# midi_switcher_trs.net
KiCad netlist of a schematic drawn in EAGLE
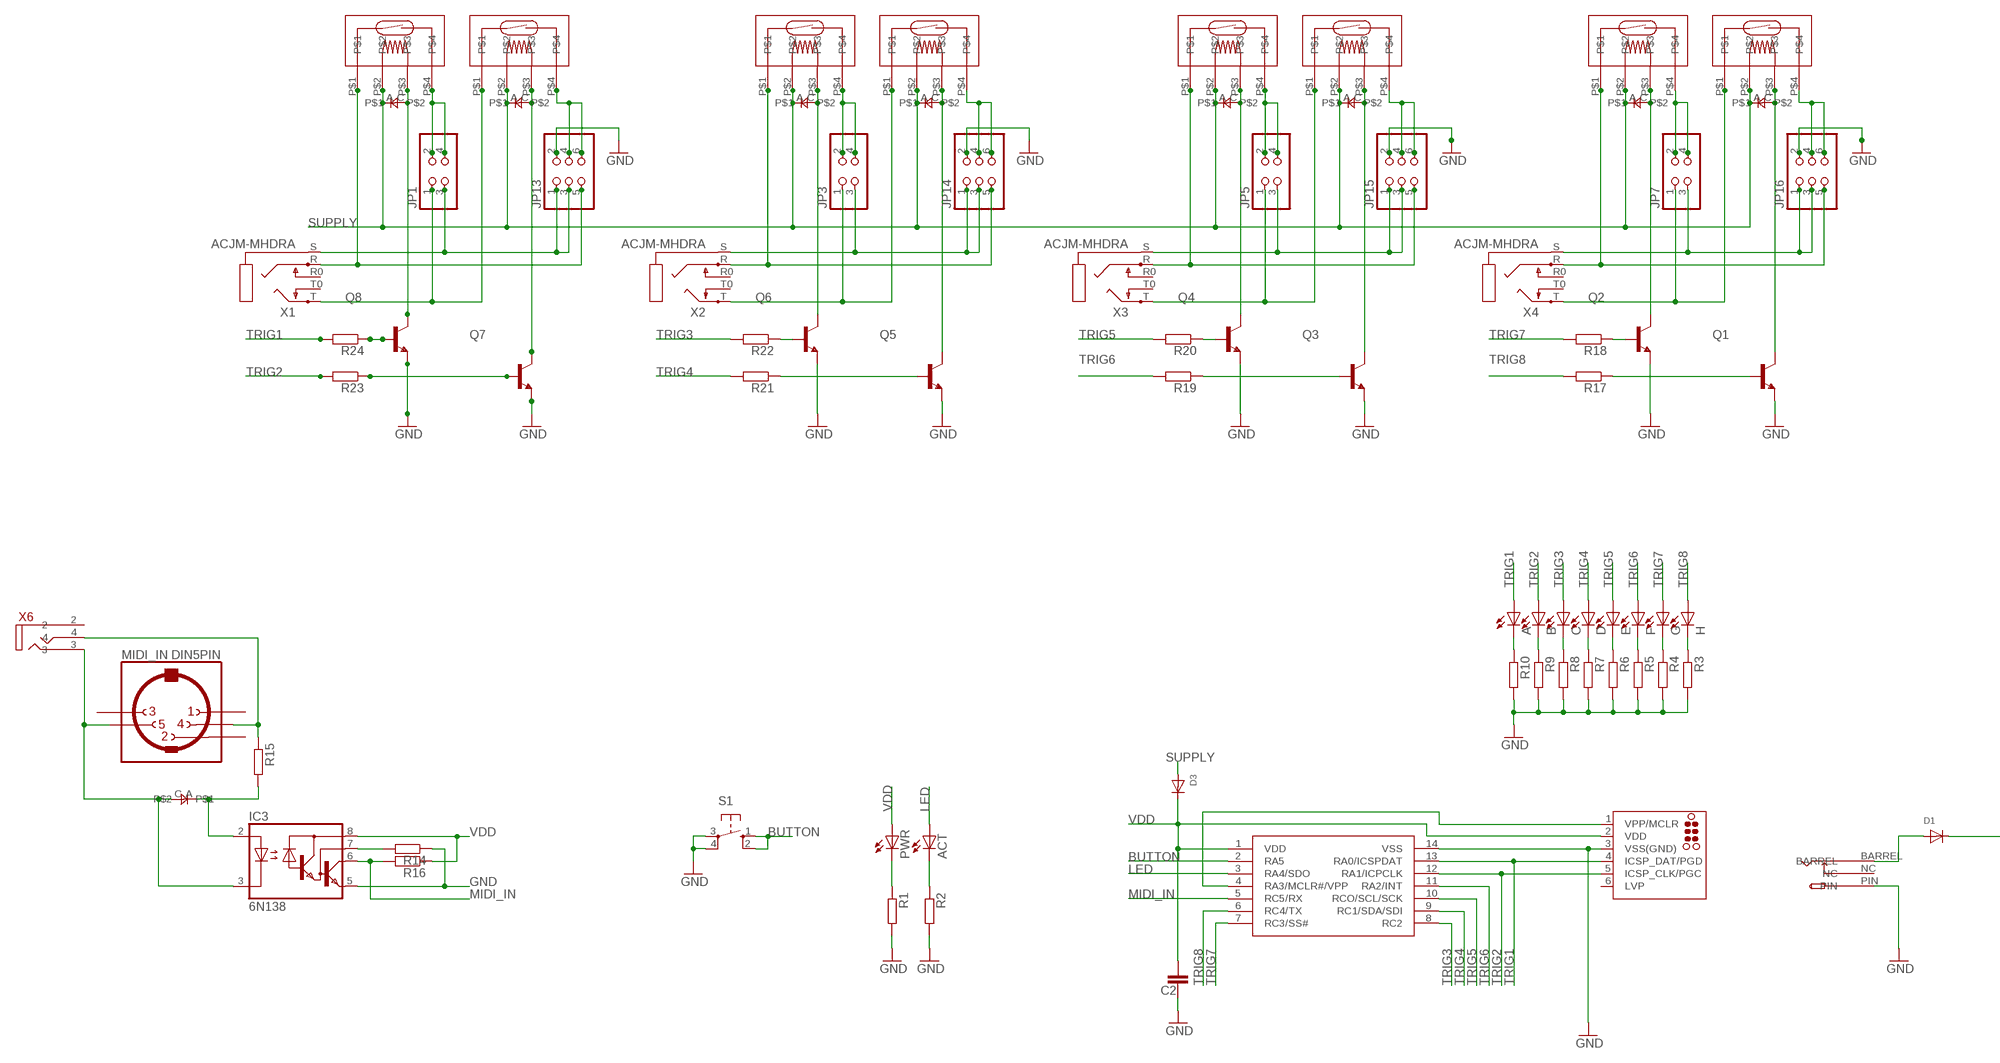
[diagram p0: schematic, sheet 1, part 1 of 2]
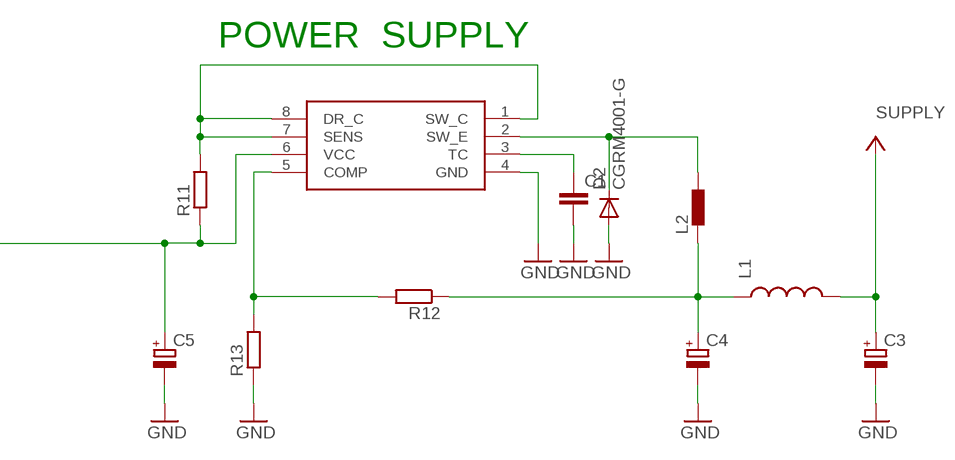
[diagram p1: schematic, sheet 1, part 2 of 2]

(export (version "E")
  (design (tool "Eeschema 10.0.6"))
  (components
    (comp (ref "A")
      (value "LED3MM")
      (footprint "eagle-import:LED3MM")
      (libsource (lib "eagle-import") (part "LED3MM"))
    )
    (comp (ref "ACT")
      (value "LED3MM")
      (footprint "eagle-import:LED3MM")
      (libsource (lib "eagle-import") (part "LED3MM"))
    )
    (comp (ref "B")
      (value "LED3MM")
      (footprint "eagle-import:LED3MM")
      (libsource (lib "eagle-import") (part "LED3MM"))
    )
    (comp (ref "C")
      (value "LED3MM")
      (footprint "eagle-import:LED3MM")
      (libsource (lib "eagle-import") (part "LED3MM"))
    )
    (comp (ref "C1")
      (value "C-EUC0805")
      (footprint "eagle-import:C0805")
      (libsource (lib "eagle-import") (part "C-EUC0805"))
    )
    (comp (ref "C2")
      (value "C-EUC0805")
      (footprint "eagle-import:C0805")
      (libsource (lib "eagle-import") (part "C-EUC0805"))
    )
    (comp (ref "C3")
      (value "CPOL-EUE2.5-7")
      (footprint "eagle-import:E2,5-7")
      (libsource (lib "eagle-import") (part "CPOL-EUE2.5-7"))
    )
    (comp (ref "C4")
      (value "CPOL-EUE2.5-7")
      (footprint "eagle-import:E2,5-7")
      (libsource (lib "eagle-import") (part "CPOL-EUE2.5-7"))
    )
    (comp (ref "C5")
      (value "CPOL-EUE2.5-7")
      (footprint "eagle-import:E2,5-7")
      (libsource (lib "eagle-import") (part "CPOL-EUE2.5-7"))
    )
    (comp (ref "D")
      (value "LED3MM")
      (footprint "eagle-import:LED3MM")
      (libsource (lib "eagle-import") (part "LED3MM"))
    )
    (comp (ref "D1")
      (value "DIODESOD-123")
      (footprint "eagle-import:SOD-123")
      (libsource (lib "eagle-import") (part "DIODESOD-123"))
    )
    (comp (ref "D2")
      (value "CGRM4001-G")
      (footprint "eagle-import:SOD-123_MINI-SMA")
      (libsource (lib "eagle-import") (part "CGRM400-G1"))
    )
    (comp (ref "D3")
      (value "DIODESOD-123")
      (footprint "eagle-import:SOD-123")
      (libsource (lib "eagle-import") (part "DIODESOD-123"))
    )
    (comp (ref "D4")
      (value "0805DIODE")
      (footprint "eagle-import:0805DIODE")
      (libsource (lib "eagle-import") (part "0805DIODE"))
    )
    (comp (ref "D5")
      (value "0805DIODE")
      (footprint "eagle-import:0805DIODE")
      (libsource (lib "eagle-import") (part "0805DIODE"))
    )
    (comp (ref "D6")
      (value "0805DIODE")
      (footprint "eagle-import:0805DIODE")
      (libsource (lib "eagle-import") (part "0805DIODE"))
    )
    (comp (ref "D7")
      (value "0805DIODE")
      (footprint "eagle-import:0805DIODE")
      (libsource (lib "eagle-import") (part "0805DIODE"))
    )
    (comp (ref "D8")
      (value "0805DIODE")
      (footprint "eagle-import:0805DIODE")
      (libsource (lib "eagle-import") (part "0805DIODE"))
    )
    (comp (ref "D9")
      (value "0805DIODE")
      (footprint "eagle-import:0805DIODE")
      (libsource (lib "eagle-import") (part "0805DIODE"))
    )
    (comp (ref "D10")
      (value "0805DIODE")
      (footprint "eagle-import:0805DIODE")
      (libsource (lib "eagle-import") (part "0805DIODE"))
    )
    (comp (ref "D11")
      (value "0805DIODE")
      (footprint "eagle-import:0805DIODE")
      (libsource (lib "eagle-import") (part "0805DIODE"))
    )
    (comp (ref "D12")
      (value "0805DIODE")
      (footprint "eagle-import:0805DIODE")
      (libsource (lib "eagle-import") (part "0805DIODE"))
    )
    (comp (ref "E")
      (value "LED3MM")
      (footprint "eagle-import:LED3MM")
      (libsource (lib "eagle-import") (part "LED3MM"))
    )
    (comp (ref "F")
      (value "LED3MM")
      (footprint "eagle-import:LED3MM")
      (libsource (lib "eagle-import") (part "LED3MM"))
    )
    (comp (ref "G")
      (value "LED3MM")
      (footprint "eagle-import:LED3MM")
      (libsource (lib "eagle-import") (part "LED3MM"))
    )
    (comp (ref "H")
      (value "LED3MM")
      (footprint "eagle-import:LED3MM")
      (libsource (lib "eagle-import") (part "LED3MM"))
    )
    (comp (ref "IC1")
      (value "SP34063A_BOOST_REG")
      (footprint "eagle-import:SOIC8")
      (libsource (lib "eagle-import") (part "SP34063A_BOOST_REG"))
    )
    (comp (ref "IC2")
      (value "PIC16F1825SO14")
      (footprint "eagle-import:SO14")
      (libsource (lib "eagle-import") (part "PIC16F1825SO14"))
    )
    (comp (ref "IC3")
      (value "6N138")
      (footprint "eagle-import:DIL08")
      (fields (field (name "MF") "VISHAY/TELEFUNKEN"))
      (libsource (lib "eagle-import") (part "6N138"))
    )
    (comp (ref "ICSP")
      (value "TC2030-MCP-NL")
      (footprint "eagle-import:TC2030-MCP-NL")
      (libsource (lib "eagle-import") (part "TC2030-MCP-NL"))
    )
    (comp (ref "JP1")
      (value "PINHD-2X2")
      (footprint "eagle-import:2X02")
      (libsource (lib "eagle-import") (part "PINHD-2X2"))
    )
    (comp (ref "JP3")
      (value "PINHD-2X2")
      (footprint "eagle-import:2X02")
      (libsource (lib "eagle-import") (part "PINHD-2X2"))
    )
    (comp (ref "JP5")
      (value "PINHD-2X2")
      (footprint "eagle-import:2X02")
      (libsource (lib "eagle-import") (part "PINHD-2X2"))
    )
    (comp (ref "JP7")
      (value "PINHD-2X2")
      (footprint "eagle-import:2X02")
      (libsource (lib "eagle-import") (part "PINHD-2X2"))
    )
    (comp (ref "JP13")
      (value "PINHD-2X3")
      (footprint "eagle-import:2X03")
      (libsource (lib "eagle-import") (part "PINHD-2X3"))
    )
    (comp (ref "JP14")
      (value "PINHD-2X3")
      (footprint "eagle-import:2X03")
      (libsource (lib "eagle-import") (part "PINHD-2X3"))
    )
    (comp (ref "JP15")
      (value "PINHD-2X3")
      (footprint "eagle-import:2X03")
      (libsource (lib "eagle-import") (part "PINHD-2X3"))
    )
    (comp (ref "JP16")
      (value "PINHD-2X3")
      (footprint "eagle-import:2X03")
      (libsource (lib "eagle-import") (part "PINHD-2X3"))
    )
    (comp (ref "L1")
      (value "INDUCTOR1210")
      (footprint "eagle-import:1210")
      (libsource (lib "eagle-import") (part "INDUCTOR1210"))
    )
    (comp (ref "L2")
      (value "DR1030")
      (footprint "eagle-import:DR1030")
      (libsource (lib "eagle-import") (part "DR1030"))
    )
    (comp (ref "MIDI_IN")
      (value "DIN5PIN")
      (footprint "eagle-import:EDGEDIN")
      (libsource (lib "eagle-import") (part "DIN5PIN"))
    )
    (comp (ref "PWR")
      (value "LED3MM")
      (footprint "eagle-import:LED3MM")
      (libsource (lib "eagle-import") (part "LED3MM"))
    )
    (comp (ref "Q1")
      (value "MMBT3904LT1-NPN-SOT23-BEC")
      (footprint "eagle-import:SOT23-BEC")
      (libsource (lib "eagle-import") (part "-NPN-SOT23-BECMMBT3904LT1"))
    )
    (comp (ref "Q2")
      (value "MMBT3904LT1-NPN-SOT23-BEC")
      (footprint "eagle-import:SOT23-BEC")
      (libsource (lib "eagle-import") (part "-NPN-SOT23-BECMMBT3904LT1"))
    )
    (comp (ref "Q3")
      (value "MMBT3904LT1-NPN-SOT23-BEC")
      (footprint "eagle-import:SOT23-BEC")
      (libsource (lib "eagle-import") (part "-NPN-SOT23-BECMMBT3904LT1"))
    )
    (comp (ref "Q4")
      (value "MMBT3904LT1-NPN-SOT23-BEC")
      (footprint "eagle-import:SOT23-BEC")
      (libsource (lib "eagle-import") (part "-NPN-SOT23-BECMMBT3904LT1"))
    )
    (comp (ref "Q5")
      (value "MMBT3904LT1-NPN-SOT23-BEC")
      (footprint "eagle-import:SOT23-BEC")
      (libsource (lib "eagle-import") (part "-NPN-SOT23-BECMMBT3904LT1"))
    )
    (comp (ref "Q6")
      (value "MMBT3904LT1-NPN-SOT23-BEC")
      (footprint "eagle-import:SOT23-BEC")
      (libsource (lib "eagle-import") (part "-NPN-SOT23-BECMMBT3904LT1"))
    )
    (comp (ref "Q7")
      (value "MMBT3904LT1-NPN-SOT23-BEC")
      (footprint "eagle-import:SOT23-BEC")
      (libsource (lib "eagle-import") (part "-NPN-SOT23-BECMMBT3904LT1"))
    )
    (comp (ref "Q8")
      (value "MMBT3904LT1-NPN-SOT23-BEC")
      (footprint "eagle-import:SOT23-BEC")
      (libsource (lib "eagle-import") (part "-NPN-SOT23-BECMMBT3904LT1"))
    )
    (comp (ref "R1")
      (value "R-EU_R0805")
      (footprint "eagle-import:R0805")
      (libsource (lib "eagle-import") (part "R-EU_R0805"))
    )
    (comp (ref "R2")
      (value "R-EU_R0805")
      (footprint "eagle-import:R0805")
      (libsource (lib "eagle-import") (part "R-EU_R0805"))
    )
    (comp (ref "R3")
      (value "R-EU_R0805")
      (footprint "eagle-import:R0805")
      (libsource (lib "eagle-import") (part "R-EU_R0805"))
    )
    (comp (ref "R4")
      (value "R-EU_R0805")
      (footprint "eagle-import:R0805")
      (libsource (lib "eagle-import") (part "R-EU_R0805"))
    )
    (comp (ref "R5")
      (value "R-EU_R0805")
      (footprint "eagle-import:R0805")
      (libsource (lib "eagle-import") (part "R-EU_R0805"))
    )
    (comp (ref "R6")
      (value "R-EU_R0805")
      (footprint "eagle-import:R0805")
      (libsource (lib "eagle-import") (part "R-EU_R0805"))
    )
    (comp (ref "R7")
      (value "R-EU_R0805")
      (footprint "eagle-import:R0805")
      (libsource (lib "eagle-import") (part "R-EU_R0805"))
    )
    (comp (ref "R8")
      (value "R-EU_R0805")
      (footprint "eagle-import:R0805")
      (libsource (lib "eagle-import") (part "R-EU_R0805"))
    )
    (comp (ref "R9")
      (value "R-EU_R0805")
      (footprint "eagle-import:R0805")
      (libsource (lib "eagle-import") (part "R-EU_R0805"))
    )
    (comp (ref "R10")
      (value "R-EU_R0805")
      (footprint "eagle-import:R0805")
      (libsource (lib "eagle-import") (part "R-EU_R0805"))
    )
    (comp (ref "R11")
      (value "R-EU_R0805")
      (footprint "eagle-import:R0805")
      (libsource (lib "eagle-import") (part "R-EU_R0805"))
    )
    (comp (ref "R12")
      (value "R-EU_R0805")
      (footprint "eagle-import:R0805")
      (libsource (lib "eagle-import") (part "R-EU_R0805"))
    )
    (comp (ref "R13")
      (value "R-EU_R0805")
      (footprint "eagle-import:R0805")
      (libsource (lib "eagle-import") (part "R-EU_R0805"))
    )
    (comp (ref "R14")
      (value "R-EU_R0805")
      (footprint "eagle-import:R0805")
      (libsource (lib "eagle-import") (part "R-EU_R0805"))
    )
    (comp (ref "R15")
      (value "R-EU_R0805")
      (footprint "eagle-import:R0805")
      (libsource (lib "eagle-import") (part "R-EU_R0805"))
    )
    (comp (ref "R16")
      (value "R-EU_R0805")
      (footprint "eagle-import:R0805")
      (libsource (lib "eagle-import") (part "R-EU_R0805"))
    )
    (comp (ref "R17")
      (value "R-EU_R0805")
      (footprint "eagle-import:R0805")
      (libsource (lib "eagle-import") (part "R-EU_R0805"))
    )
    (comp (ref "R18")
      (value "R-EU_R0805")
      (footprint "eagle-import:R0805")
      (libsource (lib "eagle-import") (part "R-EU_R0805"))
    )
    (comp (ref "R19")
      (value "R-EU_R0805")
      (footprint "eagle-import:R0805")
      (libsource (lib "eagle-import") (part "R-EU_R0805"))
    )
    (comp (ref "R20")
      (value "R-EU_R0805")
      (footprint "eagle-import:R0805")
      (libsource (lib "eagle-import") (part "R-EU_R0805"))
    )
    (comp (ref "R21")
      (value "R-EU_R0805")
      (footprint "eagle-import:R0805")
      (libsource (lib "eagle-import") (part "R-EU_R0805"))
    )
    (comp (ref "R22")
      (value "R-EU_R0805")
      (footprint "eagle-import:R0805")
      (libsource (lib "eagle-import") (part "R-EU_R0805"))
    )
    (comp (ref "R23")
      (value "R-EU_R0805")
      (footprint "eagle-import:R0805")
      (libsource (lib "eagle-import") (part "R-EU_R0805"))
    )
    (comp (ref "R24")
      (value "R-EU_R0805")
      (footprint "eagle-import:R0805")
      (libsource (lib "eagle-import") (part "R-EU_R0805"))
    )
    (comp (ref "RLY1")
      (value "9007-REED-RELAY")
      (footprint "eagle-import:9007-REED-RELAY")
      (libsource (lib "eagle-import") (part "9007-REED-RELAY"))
    )
    (comp (ref "RLY2")
      (value "9007-REED-RELAY")
      (footprint "eagle-import:9007-REED-RELAY")
      (libsource (lib "eagle-import") (part "9007-REED-RELAY"))
    )
    (comp (ref "RLY3")
      (value "9007-REED-RELAY")
      (footprint "eagle-import:9007-REED-RELAY")
      (libsource (lib "eagle-import") (part "9007-REED-RELAY"))
    )
    (comp (ref "RLY4")
      (value "9007-REED-RELAY")
      (footprint "eagle-import:9007-REED-RELAY")
      (libsource (lib "eagle-import") (part "9007-REED-RELAY"))
    )
    (comp (ref "RLY5")
      (value "9007-REED-RELAY")
      (footprint "eagle-import:9007-REED-RELAY")
      (libsource (lib "eagle-import") (part "9007-REED-RELAY"))
    )
    (comp (ref "RLY6")
      (value "9007-REED-RELAY")
      (footprint "eagle-import:9007-REED-RELAY")
      (libsource (lib "eagle-import") (part "9007-REED-RELAY"))
    )
    (comp (ref "RLY7")
      (value "9007-REED-RELAY")
      (footprint "eagle-import:9007-REED-RELAY")
      (libsource (lib "eagle-import") (part "9007-REED-RELAY"))
    )
    (comp (ref "RLY8")
      (value "9007-REED-RELAY")
      (footprint "eagle-import:9007-REED-RELAY")
      (libsource (lib "eagle-import") (part "9007-REED-RELAY"))
    )
    (comp (ref "S1")
      (value "10-XX")
      (footprint "eagle-import:B3F-10XX")
      (fields (field (name "MPN") "B3F-1000"))
      (libsource (lib "eagle-import") (part "10-XX"))
    )
    (comp (ref "U$9")
      (value "PWR_SOCKET_2_1MM")
      (footprint "eagle-import:PWR_SOCKET_2_1MM")
      (libsource (lib "eagle-import") (part "PWR_SOCKET_2_1MM"))
    )
    (comp (ref "X1")
      (value "ACJM-MHDRA")
      (footprint "eagle-import:ACJM-MHDR")
      (libsource (lib "eagle-import") (part "ACJM-MHDRA"))
    )
    (comp (ref "X2")
      (value "ACJM-MHDRA")
      (footprint "eagle-import:ACJM-MHDR")
      (libsource (lib "eagle-import") (part "ACJM-MHDRA"))
    )
    (comp (ref "X3")
      (value "ACJM-MHDRA")
      (footprint "eagle-import:ACJM-MHDR")
      (libsource (lib "eagle-import") (part "ACJM-MHDRA"))
    )
    (comp (ref "X4")
      (value "ACJM-MHDRA")
      (footprint "eagle-import:ACJM-MHDR")
      (libsource (lib "eagle-import") (part "ACJM-MHDRA"))
    )
    (comp (ref "X6")
      (value "VERTICAL_3_5MM_SOCKET")
      (footprint "eagle-import:VERTICAL_3_5MM_SOCKET")
      (libsource (lib "eagle-import") (part "VERTICAL_3_5MM_SOCKET"))
    )
  )
  (nets
    (net (code "1") (name "+5V") (class "Default")
      (node (ref "C3") (pin "+") (pinfunction "+_+") (pintype "passive"))
      (node (ref "D10") (pin "A") (pinfunction "P$2_A") (pintype "bidirectional"))
      (node (ref "D11") (pin "A") (pinfunction "P$2_A") (pintype "bidirectional"))
      (node (ref "D12") (pin "A") (pinfunction "P$2_A") (pintype "bidirectional"))
      (node (ref "D3") (pin "A") (pinfunction "A_A") (pintype "passive"))
      (node (ref "D5") (pin "A") (pinfunction "P$2_A") (pintype "bidirectional"))
      (node (ref "D6") (pin "A") (pinfunction "P$2_A") (pintype "bidirectional"))
      (node (ref "D7") (pin "A") (pinfunction "P$2_A") (pintype "bidirectional"))
      (node (ref "D8") (pin "A") (pinfunction "P$2_A") (pintype "bidirectional"))
      (node (ref "D9") (pin "A") (pinfunction "P$2_A") (pintype "bidirectional"))
      (node (ref "L1") (pin "2") (pinfunction "2_2") (pintype "passive"))
      (node (ref "RLY1") (pin "P$2") (pinfunction "P$2_P$2") (pintype "bidirectional"))
      (node (ref "RLY2") (pin "P$2") (pinfunction "P$2_P$2") (pintype "bidirectional"))
      (node (ref "RLY3") (pin "P$2") (pinfunction "P$2_P$2") (pintype "bidirectional"))
      (node (ref "RLY4") (pin "P$2") (pinfunction "P$2_P$2") (pintype "bidirectional"))
      (node (ref "RLY5") (pin "P$2") (pinfunction "P$2_P$2") (pintype "bidirectional"))
      (node (ref "RLY6") (pin "P$2") (pinfunction "P$2_P$2") (pintype "bidirectional"))
      (node (ref "RLY7") (pin "P$2") (pinfunction "P$2_P$2") (pintype "bidirectional"))
      (node (ref "RLY8") (pin "P$2") (pinfunction "P$2_P$2") (pintype "bidirectional"))
    )
    (net (code "2") (name "/BUTTON") (class "Default")
      (node (ref "IC2") (pin "2") (pinfunction "RA5_2") (pintype "bidirectional"))
      (node (ref "S1") (pin "1") (pinfunction "S_1") (pintype "passive"))
      (node (ref "S1") (pin "2") (pinfunction "S1_2") (pintype "passive"))
    )
    (net (code "3") (name "/LED") (class "Default")
      (node (ref "ACT") (pin "A") (pinfunction "A_A") (pintype "passive"))
      (node (ref "IC2") (pin "3") (pinfunction "RA4/SDO_3") (pintype "bidirectional"))
    )
    (net (code "4") (name "/MIDI_IN") (class "Default")
      (node (ref "IC2") (pin "5") (pinfunction "RC5/RX_5") (pintype "bidirectional"))
      (node (ref "IC3") (pin "6") (pinfunction "VO_6") (pintype "passive"))
      (node (ref "R16") (pin "2") (pinfunction "2_2") (pintype "passive"))
    )
    (net (code "5") (name "/TRIG1") (class "Default")
      (node (ref "A") (pin "A") (pinfunction "A_A") (pintype "passive"))
      (node (ref "IC2") (pin "13") (pinfunction "RA0/ICSPDAT_13") (pintype "bidirectional"))
      (node (ref "ICSP") (pin "4") (pinfunction "ICSP_DAT/PGD_4") (pintype "bidirectional"))
      (node (ref "R24") (pin "2") (pinfunction "2_2") (pintype "passive"))
    )
    (net (code "6") (name "/TRIG2") (class "Default")
      (node (ref "B") (pin "A") (pinfunction "A_A") (pintype "passive"))
      (node (ref "IC2") (pin "12") (pinfunction "RA1/ICPCLK_12") (pintype "bidirectional"))
      (node (ref "ICSP") (pin "5") (pinfunction "ICSP_CLK/PGC_5") (pintype "output"))
      (node (ref "R23") (pin "2") (pinfunction "2_2") (pintype "passive"))
    )
    (net (code "7") (name "/TRIG3") (class "Default")
      (node (ref "C") (pin "A") (pinfunction "A_A") (pintype "passive"))
      (node (ref "IC2") (pin "8") (pinfunction "RC2_8") (pintype "bidirectional"))
      (node (ref "R22") (pin "2") (pinfunction "2_2") (pintype "passive"))
    )
    (net (code "8") (name "/TRIG4") (class "Default")
      (node (ref "D") (pin "A") (pinfunction "A_A") (pintype "passive"))
      (node (ref "IC2") (pin "9") (pinfunction "RC1/SDA/SDI_9") (pintype "bidirectional"))
      (node (ref "R21") (pin "2") (pinfunction "2_2") (pintype "passive"))
    )
    (net (code "9") (name "/TRIG5") (class "Default")
      (node (ref "E") (pin "A") (pinfunction "A_A") (pintype "passive"))
      (node (ref "IC2") (pin "10") (pinfunction "RCO/SCL/SCK_10") (pintype "bidirectional"))
      (node (ref "R20") (pin "2") (pinfunction "2_2") (pintype "passive"))
    )
    (net (code "10") (name "/TRIG6") (class "Default")
      (node (ref "F") (pin "A") (pinfunction "A_A") (pintype "passive"))
      (node (ref "IC2") (pin "11") (pinfunction "RA2/INT_11") (pintype "bidirectional"))
      (node (ref "R19") (pin "2") (pinfunction "2_2") (pintype "passive"))
    )
    (net (code "11") (name "/TRIG7") (class "Default")
      (node (ref "G") (pin "A") (pinfunction "A_A") (pintype "passive"))
      (node (ref "IC2") (pin "7") (pinfunction "RC3/SS#_7") (pintype "bidirectional"))
      (node (ref "R18") (pin "2") (pinfunction "2_2") (pintype "passive"))
    )
    (net (code "12") (name "/TRIG8") (class "Default")
      (node (ref "H") (pin "A") (pinfunction "A_A") (pintype "passive"))
      (node (ref "IC2") (pin "6") (pinfunction "RC4/TX_6") (pintype "bidirectional"))
      (node (ref "R17") (pin "2") (pinfunction "2_2") (pintype "passive"))
    )
    (net (code "13") (name "/VDD") (class "Default")
      (node (ref "C2") (pin "1") (pinfunction "1_1") (pintype "passive"))
      (node (ref "D3") (pin "C") (pinfunction "C_C") (pintype "passive"))
      (node (ref "IC2") (pin "1") (pinfunction "VDD_1") (pintype "power_in"))
      (node (ref "IC3") (pin "8") (pinfunction "VCC_8") (pintype "passive"))
      (node (ref "ICSP") (pin "2") (pinfunction "VDD_2") (pintype "power_in"))
      (node (ref "PWR") (pin "A") (pinfunction "A_A") (pintype "passive"))
      (node (ref "R16") (pin "1") (pinfunction "1_1") (pintype "passive"))
    )
    (net (code "14") (name "GND") (class "Default")
      (node (ref "C1") (pin "2") (pinfunction "2_2") (pintype "passive"))
      (node (ref "C2") (pin "2") (pinfunction "2_2") (pintype "passive"))
      (node (ref "C3") (pin "-") (pinfunction "-_-") (pintype "passive"))
      (node (ref "C4") (pin "-") (pinfunction "-_-") (pintype "passive"))
      (node (ref "C5") (pin "-") (pinfunction "-_-") (pintype "passive"))
      (node (ref "D2") (pin "A") (pinfunction "A_A") (pintype "passive"))
      (node (ref "IC1") (pin "4") (pinfunction "GND_4") (pintype "bidirectional"))
      (node (ref "IC2") (pin "14") (pinfunction "VSS_14") (pintype "power_in"))
      (node (ref "IC3") (pin "5") (pinfunction "GND_5") (pintype "passive"))
      (node (ref "ICSP") (pin "3") (pinfunction "VSS(GND)_3") (pintype "power_in"))
      (node (ref "JP13") (pin "2") (pinfunction "2_2") (pintype "passive"))
      (node (ref "JP14") (pin "2") (pinfunction "2_2") (pintype "passive"))
      (node (ref "JP15") (pin "2") (pinfunction "2_2") (pintype "passive"))
      (node (ref "JP16") (pin "2") (pinfunction "2_2") (pintype "passive"))
      (node (ref "Q1") (pin "E") (pinfunction "E_E") (pintype "passive"))
      (node (ref "Q2") (pin "E") (pinfunction "E_E") (pintype "passive"))
      (node (ref "Q3") (pin "E") (pinfunction "E_E") (pintype "passive"))
      (node (ref "Q4") (pin "E") (pinfunction "E_E") (pintype "passive"))
      (node (ref "Q5") (pin "E") (pinfunction "E_E") (pintype "passive"))
      (node (ref "Q6") (pin "E") (pinfunction "E_E") (pintype "passive"))
      (node (ref "Q7") (pin "E") (pinfunction "E_E") (pintype "passive"))
      (node (ref "Q8") (pin "E") (pinfunction "E_E") (pintype "passive"))
      (node (ref "R1") (pin "2") (pinfunction "2_2") (pintype "passive"))
      (node (ref "R10") (pin "2") (pinfunction "2_2") (pintype "passive"))
      (node (ref "R13") (pin "1") (pinfunction "1_1") (pintype "passive"))
      (node (ref "R14") (pin "1") (pinfunction "1_1") (pintype "passive"))
      (node (ref "R2") (pin "2") (pinfunction "2_2") (pintype "passive"))
      (node (ref "R3") (pin "2") (pinfunction "2_2") (pintype "passive"))
      (node (ref "R4") (pin "2") (pinfunction "2_2") (pintype "passive"))
      (node (ref "R5") (pin "2") (pinfunction "2_2") (pintype "passive"))
      (node (ref "R6") (pin "2") (pinfunction "2_2") (pintype "passive"))
      (node (ref "R7") (pin "2") (pinfunction "2_2") (pintype "passive"))
      (node (ref "R8") (pin "2") (pinfunction "2_2") (pintype "passive"))
      (node (ref "R9") (pin "2") (pinfunction "2_2") (pintype "passive"))
      (node (ref "S1") (pin "3") (pinfunction "P_3") (pintype "passive"))
      (node (ref "S1") (pin "4") (pinfunction "P1_4") (pintype "passive"))
      (node (ref "U$9") (pin "PIN") (pinfunction "PIN_PIN") (pintype "bidirectional"))
    )
    (net (code "15") (name "Net-(A-C)") (class "Default")
      (node (ref "A") (pin "K") (pinfunction "C_K") (pintype "passive"))
      (node (ref "R10") (pin "1") (pinfunction "1_1") (pintype "passive"))
    )
    (net (code "16") (name "Net-(ACT-C)") (class "Default")
      (node (ref "ACT") (pin "K") (pinfunction "C_K") (pintype "passive"))
      (node (ref "R2") (pin "1") (pinfunction "1_1") (pintype "passive"))
    )
    (net (code "17") (name "Net-(B-C)") (class "Default")
      (node (ref "B") (pin "K") (pinfunction "C_K") (pintype "passive"))
      (node (ref "R9") (pin "1") (pinfunction "1_1") (pintype "passive"))
    )
    (net (code "18") (name "Net-(C-C)") (class "Default")
      (node (ref "C") (pin "K") (pinfunction "C_K") (pintype "passive"))
      (node (ref "R8") (pin "1") (pinfunction "1_1") (pintype "passive"))
    )
    (net (code "19") (name "Net-(C4-Pad+)") (class "Default")
      (node (ref "C4") (pin "+") (pinfunction "+_+") (pintype "passive"))
      (node (ref "L1") (pin "1") (pinfunction "1_1") (pintype "passive"))
      (node (ref "L2") (pin "1") (pinfunction "1_1") (pintype "passive"))
      (node (ref "R12") (pin "1") (pinfunction "1_1") (pintype "passive"))
    )
    (net (code "20") (name "Net-(D-C)") (class "Default")
      (node (ref "D") (pin "K") (pinfunction "C_K") (pintype "passive"))
      (node (ref "R7") (pin "1") (pinfunction "1_1") (pintype "passive"))
    )
    (net (code "21") (name "Net-(D1-PadA)") (class "Default")
      (node (ref "D1") (pin "A") (pinfunction "A_A") (pintype "passive"))
      (node (ref "U$9") (pin "BARREL") (pinfunction "BARREL_BARREL") (pintype "bidirectional"))
    )
    (net (code "22") (name "Net-(D4-P$1)") (class "Default")
      (node (ref "D4") (pin "C") (pinfunction "P$1_C") (pintype "bidirectional"))
      (node (ref "IC3") (pin "3") (pinfunction "C_3") (pintype "passive"))
      (node (ref "MIDI_IN") (pin "5") (pinfunction "5_5") (pintype "passive"))
      (node (ref "X6") (pin "3") (pinfunction "3_3") (pintype "bidirectional"))
    )
    (net (code "23") (name "Net-(D4-P$2)") (class "Default")
      (node (ref "D4") (pin "A") (pinfunction "P$2_A") (pintype "bidirectional"))
      (node (ref "IC3") (pin "2") (pinfunction "A_2") (pintype "passive"))
      (node (ref "R15") (pin "2") (pinfunction "2_2") (pintype "passive"))
    )
    (net (code "24") (name "Net-(D5-P$1)") (class "Default")
      (node (ref "D5") (pin "C") (pinfunction "P$1_C") (pintype "bidirectional"))
      (node (ref "Q1") (pin "C") (pinfunction "C_C") (pintype "passive"))
      (node (ref "RLY8") (pin "P$3") (pinfunction "P$3_P$3") (pintype "bidirectional"))
    )
    (net (code "25") (name "Net-(D6-P$1)") (class "Default")
      (node (ref "D6") (pin "C") (pinfunction "P$1_C") (pintype "bidirectional"))
      (node (ref "Q2") (pin "C") (pinfunction "C_C") (pintype "passive"))
      (node (ref "RLY7") (pin "P$3") (pinfunction "P$3_P$3") (pintype "bidirectional"))
    )
    (net (code "26") (name "Net-(D7-P$1)") (class "Default")
      (node (ref "D7") (pin "C") (pinfunction "P$1_C") (pintype "bidirectional"))
      (node (ref "Q3") (pin "C") (pinfunction "C_C") (pintype "passive"))
      (node (ref "RLY6") (pin "P$3") (pinfunction "P$3_P$3") (pintype "bidirectional"))
    )
    (net (code "27") (name "Net-(D8-P$1)") (class "Default")
      (node (ref "D8") (pin "C") (pinfunction "P$1_C") (pintype "bidirectional"))
      (node (ref "Q4") (pin "C") (pinfunction "C_C") (pintype "passive"))
      (node (ref "RLY5") (pin "P$3") (pinfunction "P$3_P$3") (pintype "bidirectional"))
    )
    (net (code "28") (name "Net-(D9-P$1)") (class "Default")
      (node (ref "D9") (pin "C") (pinfunction "P$1_C") (pintype "bidirectional"))
      (node (ref "Q5") (pin "C") (pinfunction "C_C") (pintype "passive"))
      (node (ref "RLY4") (pin "P$3") (pinfunction "P$3_P$3") (pintype "bidirectional"))
    )
    (net (code "29") (name "Net-(D10-P$1)") (class "Default")
      (node (ref "D10") (pin "C") (pinfunction "P$1_C") (pintype "bidirectional"))
      (node (ref "Q6") (pin "C") (pinfunction "C_C") (pintype "passive"))
      (node (ref "RLY3") (pin "P$3") (pinfunction "P$3_P$3") (pintype "bidirectional"))
    )
    (net (code "30") (name "Net-(D11-P$1)") (class "Default")
      (node (ref "D11") (pin "C") (pinfunction "P$1_C") (pintype "bidirectional"))
      (node (ref "Q7") (pin "C") (pinfunction "C_C") (pintype "passive"))
      (node (ref "RLY2") (pin "P$3") (pinfunction "P$3_P$3") (pintype "bidirectional"))
    )
    (net (code "31") (name "Net-(D12-P$1)") (class "Default")
      (node (ref "D12") (pin "C") (pinfunction "P$1_C") (pintype "bidirectional"))
      (node (ref "Q8") (pin "C") (pinfunction "C_C") (pintype "passive"))
      (node (ref "RLY1") (pin "P$3") (pinfunction "P$3_P$3") (pintype "bidirectional"))
    )
    (net (code "32") (name "Net-(E-C)") (class "Default")
      (node (ref "E") (pin "K") (pinfunction "C_K") (pintype "passive"))
      (node (ref "R6") (pin "1") (pinfunction "1_1") (pintype "passive"))
    )
    (net (code "33") (name "Net-(F-C)") (class "Default")
      (node (ref "F") (pin "K") (pinfunction "C_K") (pintype "passive"))
      (node (ref "R5") (pin "1") (pinfunction "1_1") (pintype "passive"))
    )
    (net (code "34") (name "Net-(G-C)") (class "Default")
      (node (ref "G") (pin "K") (pinfunction "C_K") (pintype "passive"))
      (node (ref "R4") (pin "1") (pinfunction "1_1") (pintype "passive"))
    )
    (net (code "35") (name "Net-(H-C)") (class "Default")
      (node (ref "H") (pin "K") (pinfunction "C_K") (pintype "passive"))
      (node (ref "R3") (pin "1") (pinfunction "1_1") (pintype "passive"))
    )
    (net (code "36") (name "Net-(IC1-COMP)") (class "Default")
      (node (ref "IC1") (pin "5") (pinfunction "COMP_5") (pintype "bidirectional"))
      (node (ref "R12") (pin "2") (pinfunction "2_2") (pintype "passive"))
      (node (ref "R13") (pin "2") (pinfunction "2_2") (pintype "passive"))
    )
    (net (code "37") (name "Net-(IC1-DR_C)") (class "Default")
      (node (ref "IC1") (pin "1") (pinfunction "SW_C_1") (pintype "bidirectional"))
      (node (ref "IC1") (pin "7") (pinfunction "SENS_7") (pintype "bidirectional"))
      (node (ref "IC1") (pin "8") (pinfunction "DR_C_8") (pintype "bidirectional"))
      (node (ref "R11") (pin "2") (pinfunction "2_2") (pintype "passive"))
    )
    (net (code "38") (name "Net-(IC1-SW_E)") (class "Default")
      (node (ref "D2") (pin "C") (pinfunction "C_C") (pintype "passive"))
      (node (ref "IC1") (pin "2") (pinfunction "SW_E_2") (pintype "bidirectional"))
      (node (ref "L2") (pin "2") (pinfunction "2_2") (pintype "passive"))
    )
    (net (code "39") (name "Net-(IC1-TC)") (class "Default")
      (node (ref "C1") (pin "1") (pinfunction "1_1") (pintype "passive"))
      (node (ref "IC1") (pin "3") (pinfunction "TC_3") (pintype "bidirectional"))
    )
    (net (code "40") (name "Net-(IC1-VCC)") (class "Default")
      (node (ref "C5") (pin "+") (pinfunction "+_+") (pintype "passive"))
      (node (ref "D1") (pin "C") (pinfunction "C_C") (pintype "passive"))
      (node (ref "IC1") (pin "6") (pinfunction "VCC_6") (pintype "bidirectional"))
      (node (ref "R11") (pin "1") (pinfunction "1_1") (pintype "passive"))
    )
    (net (code "41") (name "Net-(IC2-RA3{slash}MCLR#{slash}VPP)") (class "Default")
      (node (ref "IC2") (pin "4") (pinfunction "RA3/MCLR#/VPP_4") (pintype "input"))
      (node (ref "ICSP") (pin "1") (pinfunction "VPP/MCLR_1") (pintype "passive"))
    )
    (net (code "42") (name "Net-(IC3-VB)") (class "Default")
      (node (ref "IC3") (pin "7") (pinfunction "VB_7") (pintype "passive"))
      (node (ref "R14") (pin "2") (pinfunction "2_2") (pintype "passive"))
    )
    (net (code "43") (name "Net-(JP1-Pad2)") (class "Default")
      (node (ref "JP1") (pin "2") (pinfunction "2_2") (pintype "passive"))
      (node (ref "JP1") (pin "4") (pinfunction "4_4") (pintype "passive"))
      (node (ref "RLY1") (pin "P$4") (pinfunction "P$4_P$4") (pintype "bidirectional"))
    )
    (net (code "44") (name "Net-(JP3-Pad2)") (class "Default")
      (node (ref "JP3") (pin "2") (pinfunction "2_2") (pintype "passive"))
      (node (ref "JP3") (pin "4") (pinfunction "4_4") (pintype "passive"))
      (node (ref "RLY3") (pin "P$4") (pinfunction "P$4_P$4") (pintype "bidirectional"))
    )
    (net (code "45") (name "Net-(JP5-Pad2)") (class "Default")
      (node (ref "JP5") (pin "2") (pinfunction "2_2") (pintype "passive"))
      (node (ref "JP5") (pin "4") (pinfunction "4_4") (pintype "passive"))
      (node (ref "RLY5") (pin "P$4") (pinfunction "P$4_P$4") (pintype "bidirectional"))
    )
    (net (code "46") (name "Net-(JP7-Pad2)") (class "Default")
      (node (ref "JP7") (pin "2") (pinfunction "2_2") (pintype "passive"))
      (node (ref "JP7") (pin "4") (pinfunction "4_4") (pintype "passive"))
      (node (ref "RLY7") (pin "P$4") (pinfunction "P$4_P$4") (pintype "bidirectional"))
    )
    (net (code "47") (name "Net-(JP13-Pad4)") (class "Default")
      (node (ref "JP13") (pin "4") (pinfunction "4_4") (pintype "passive"))
      (node (ref "JP13") (pin "6") (pinfunction "6_6") (pintype "passive"))
      (node (ref "RLY2") (pin "P$4") (pinfunction "P$4_P$4") (pintype "bidirectional"))
    )
    (net (code "48") (name "Net-(JP14-Pad4)") (class "Default")
      (node (ref "JP14") (pin "4") (pinfunction "4_4") (pintype "passive"))
      (node (ref "JP14") (pin "6") (pinfunction "6_6") (pintype "passive"))
      (node (ref "RLY4") (pin "P$4") (pinfunction "P$4_P$4") (pintype "bidirectional"))
    )
    (net (code "49") (name "Net-(JP15-Pad4)") (class "Default")
      (node (ref "JP15") (pin "4") (pinfunction "4_4") (pintype "passive"))
      (node (ref "JP15") (pin "6") (pinfunction "6_6") (pintype "passive"))
      (node (ref "RLY6") (pin "P$4") (pinfunction "P$4_P$4") (pintype "bidirectional"))
    )
    (net (code "50") (name "Net-(JP16-Pad4)") (class "Default")
      (node (ref "JP16") (pin "4") (pinfunction "4_4") (pintype "passive"))
      (node (ref "JP16") (pin "6") (pinfunction "6_6") (pintype "passive"))
      (node (ref "RLY8") (pin "P$4") (pinfunction "P$4_P$4") (pintype "bidirectional"))
    )
    (net (code "51") (name "Net-(MIDI_IN-Pad4)") (class "Default")
      (node (ref "MIDI_IN") (pin "4") (pinfunction "4_4") (pintype "passive"))
      (node (ref "R15") (pin "1") (pinfunction "1_1") (pintype "passive"))
      (node (ref "X6") (pin "4") (pinfunction "4_4") (pintype "bidirectional"))
    )
    (net (code "52") (name "Net-(PWR-C)") (class "Default")
      (node (ref "PWR") (pin "K") (pinfunction "C_K") (pintype "passive"))
      (node (ref "R1") (pin "1") (pinfunction "1_1") (pintype "passive"))
    )
    (net (code "53") (name "Net-(Q1-PadB)") (class "Default")
      (node (ref "Q1") (pin "B") (pinfunction "B_B") (pintype "passive"))
      (node (ref "R17") (pin "1") (pinfunction "1_1") (pintype "passive"))
    )
    (net (code "54") (name "Net-(Q2-PadB)") (class "Default")
      (node (ref "Q2") (pin "B") (pinfunction "B_B") (pintype "passive"))
      (node (ref "R18") (pin "1") (pinfunction "1_1") (pintype "passive"))
    )
    (net (code "55") (name "Net-(Q3-PadB)") (class "Default")
      (node (ref "Q3") (pin "B") (pinfunction "B_B") (pintype "passive"))
      (node (ref "R19") (pin "1") (pinfunction "1_1") (pintype "passive"))
    )
    (net (code "56") (name "Net-(Q4-PadB)") (class "Default")
      (node (ref "Q4") (pin "B") (pinfunction "B_B") (pintype "passive"))
      (node (ref "R20") (pin "1") (pinfunction "1_1") (pintype "passive"))
    )
    (net (code "57") (name "Net-(Q5-PadB)") (class "Default")
      (node (ref "Q5") (pin "B") (pinfunction "B_B") (pintype "passive"))
      (node (ref "R21") (pin "1") (pinfunction "1_1") (pintype "passive"))
    )
    (net (code "58") (name "Net-(Q6-PadB)") (class "Default")
      (node (ref "Q6") (pin "B") (pinfunction "B_B") (pintype "passive"))
      (node (ref "R22") (pin "1") (pinfunction "1_1") (pintype "passive"))
    )
    (net (code "59") (name "Net-(Q7-PadB)") (class "Default")
      (node (ref "Q7") (pin "B") (pinfunction "B_B") (pintype "passive"))
      (node (ref "R23") (pin "1") (pinfunction "1_1") (pintype "passive"))
    )
    (net (code "60") (name "Net-(Q8-PadB)") (class "Default")
      (node (ref "Q8") (pin "B") (pinfunction "B_B") (pintype "passive"))
      (node (ref "R24") (pin "1") (pinfunction "1_1") (pintype "passive"))
    )
    (net (code "61") (name "Net-(X1-1)") (class "Default")
      (node (ref "JP1") (pin "3") (pinfunction "3_3") (pintype "passive"))
      (node (ref "JP13") (pin "1") (pinfunction "1_1") (pintype "passive"))
      (node (ref "JP13") (pin "3") (pinfunction "3_3") (pintype "passive"))
      (node (ref "X1") (pin "S") (pinfunction "1_S") (pintype "passive"))
    )
    (net (code "62") (name "Net-(X1-2)") (class "Default")
      (node (ref "JP13") (pin "5") (pinfunction "5_5") (pintype "passive"))
      (node (ref "RLY1") (pin "P$1") (pinfunction "P$1_P$1") (pintype "bidirectional"))
      (node (ref "X1") (pin "R") (pinfunction "2_R") (pintype "passive"))
    )
    (net (code "63") (name "Net-(X1-5)") (class "Default")
      (node (ref "JP1") (pin "1") (pinfunction "1_1") (pintype "passive"))
      (node (ref "RLY2") (pin "P$1") (pinfunction "P$1_P$1") (pintype "bidirectional"))
      (node (ref "X1") (pin "T") (pinfunction "5_T") (pintype "passive"))
    )
    (net (code "64") (name "Net-(X2-1)") (class "Default")
      (node (ref "JP14") (pin "1") (pinfunction "1_1") (pintype "passive"))
      (node (ref "JP14") (pin "3") (pinfunction "3_3") (pintype "passive"))
      (node (ref "JP3") (pin "3") (pinfunction "3_3") (pintype "passive"))
      (node (ref "X2") (pin "S") (pinfunction "1_S") (pintype "passive"))
    )
    (net (code "65") (name "Net-(X2-2)") (class "Default")
      (node (ref "JP14") (pin "5") (pinfunction "5_5") (pintype "passive"))
      (node (ref "RLY3") (pin "P$1") (pinfunction "P$1_P$1") (pintype "bidirectional"))
      (node (ref "X2") (pin "R") (pinfunction "2_R") (pintype "passive"))
    )
    (net (code "66") (name "Net-(X2-5)") (class "Default")
      (node (ref "JP3") (pin "1") (pinfunction "1_1") (pintype "passive"))
      (node (ref "RLY4") (pin "P$1") (pinfunction "P$1_P$1") (pintype "bidirectional"))
      (node (ref "X2") (pin "T") (pinfunction "5_T") (pintype "passive"))
    )
    (net (code "67") (name "Net-(X3-1)") (class "Default")
      (node (ref "JP15") (pin "1") (pinfunction "1_1") (pintype "passive"))
      (node (ref "JP15") (pin "3") (pinfunction "3_3") (pintype "passive"))
      (node (ref "JP5") (pin "3") (pinfunction "3_3") (pintype "passive"))
      (node (ref "X3") (pin "S") (pinfunction "1_S") (pintype "passive"))
    )
    (net (code "68") (name "Net-(X3-2)") (class "Default")
      (node (ref "JP15") (pin "5") (pinfunction "5_5") (pintype "passive"))
      (node (ref "RLY5") (pin "P$1") (pinfunction "P$1_P$1") (pintype "bidirectional"))
      (node (ref "X3") (pin "R") (pinfunction "2_R") (pintype "passive"))
    )
    (net (code "69") (name "Net-(X3-5)") (class "Default")
      (node (ref "JP5") (pin "1") (pinfunction "1_1") (pintype "passive"))
      (node (ref "RLY6") (pin "P$1") (pinfunction "P$1_P$1") (pintype "bidirectional"))
      (node (ref "X3") (pin "T") (pinfunction "5_T") (pintype "passive"))
    )
    (net (code "70") (name "Net-(X4-1)") (class "Default")
      (node (ref "JP16") (pin "1") (pinfunction "1_1") (pintype "passive"))
      (node (ref "JP16") (pin "3") (pinfunction "3_3") (pintype "passive"))
      (node (ref "JP7") (pin "3") (pinfunction "3_3") (pintype "passive"))
      (node (ref "X4") (pin "S") (pinfunction "1_S") (pintype "passive"))
    )
    (net (code "71") (name "Net-(X4-2)") (class "Default")
      (node (ref "JP16") (pin "5") (pinfunction "5_5") (pintype "passive"))
      (node (ref "RLY7") (pin "P$1") (pinfunction "P$1_P$1") (pintype "bidirectional"))
      (node (ref "X4") (pin "R") (pinfunction "2_R") (pintype "passive"))
    )
    (net (code "72") (name "Net-(X4-5)") (class "Default")
      (node (ref "JP7") (pin "1") (pinfunction "1_1") (pintype "passive"))
      (node (ref "RLY8") (pin "P$1") (pinfunction "P$1_P$1") (pintype "bidirectional"))
      (node (ref "X4") (pin "T") (pinfunction "5_T") (pintype "passive"))
    )
    (net (code "73") (name "unconnected-(ICSP-LVP-Pad6)") (class "Default")
      (node (ref "ICSP") (pin "6") (pinfunction "LVP_6") (pintype "bidirectional"))
    )
    (net (code "74") (name "unconnected-(MIDI_IN-Pad1)") (class "Default")
      (node (ref "MIDI_IN") (pin "1") (pinfunction "1_1") (pintype "passive"))
    )
    (net (code "75") (name "unconnected-(MIDI_IN-Pad2)") (class "Default")
      (node (ref "MIDI_IN") (pin "2") (pinfunction "2_2") (pintype "passive"))
    )
    (net (code "76") (name "unconnected-(MIDI_IN-Pad3)") (class "Default")
      (node (ref "MIDI_IN") (pin "3") (pinfunction "3_3") (pintype "passive"))
    )
    (net (code "77") (name "unconnected-(U$9-PadNC)") (class "Default")
      (node (ref "U$9") (pin "NC") (pinfunction "NC_NC") (pintype "bidirectional"))
    )
    (net (code "78") (name "unconnected-(X1-3-PadR0)") (class "Default")
      (node (ref "X1") (pin "R0") (pinfunction "3_R0") (pintype "passive"))
    )
    (net (code "79") (name "unconnected-(X1-4-PadT0)") (class "Default")
      (node (ref "X1") (pin "T0") (pinfunction "4_T0") (pintype "passive"))
    )
    (net (code "80") (name "unconnected-(X2-3-PadR0)") (class "Default")
      (node (ref "X2") (pin "R0") (pinfunction "3_R0") (pintype "passive"))
    )
    (net (code "81") (name "unconnected-(X2-4-PadT0)") (class "Default")
      (node (ref "X2") (pin "T0") (pinfunction "4_T0") (pintype "passive"))
    )
    (net (code "82") (name "unconnected-(X3-3-PadR0)") (class "Default")
      (node (ref "X3") (pin "R0") (pinfunction "3_R0") (pintype "passive"))
    )
    (net (code "83") (name "unconnected-(X3-4-PadT0)") (class "Default")
      (node (ref "X3") (pin "T0") (pinfunction "4_T0") (pintype "passive"))
    )
    (net (code "84") (name "unconnected-(X4-3-PadR0)") (class "Default")
      (node (ref "X4") (pin "R0") (pinfunction "3_R0") (pintype "passive"))
    )
    (net (code "85") (name "unconnected-(X4-4-PadT0)") (class "Default")
      (node (ref "X4") (pin "T0") (pinfunction "4_T0") (pintype "passive"))
    )
    (net (code "86") (name "unconnected-(X6-Pad2)") (class "Default")
      (node (ref "X6") (pin "2") (pinfunction "2_2") (pintype "bidirectional"))
    )
  )
)
